# Booster_wire_schematic.net
KiCad netlist of a schematic drawn in EasyEDA
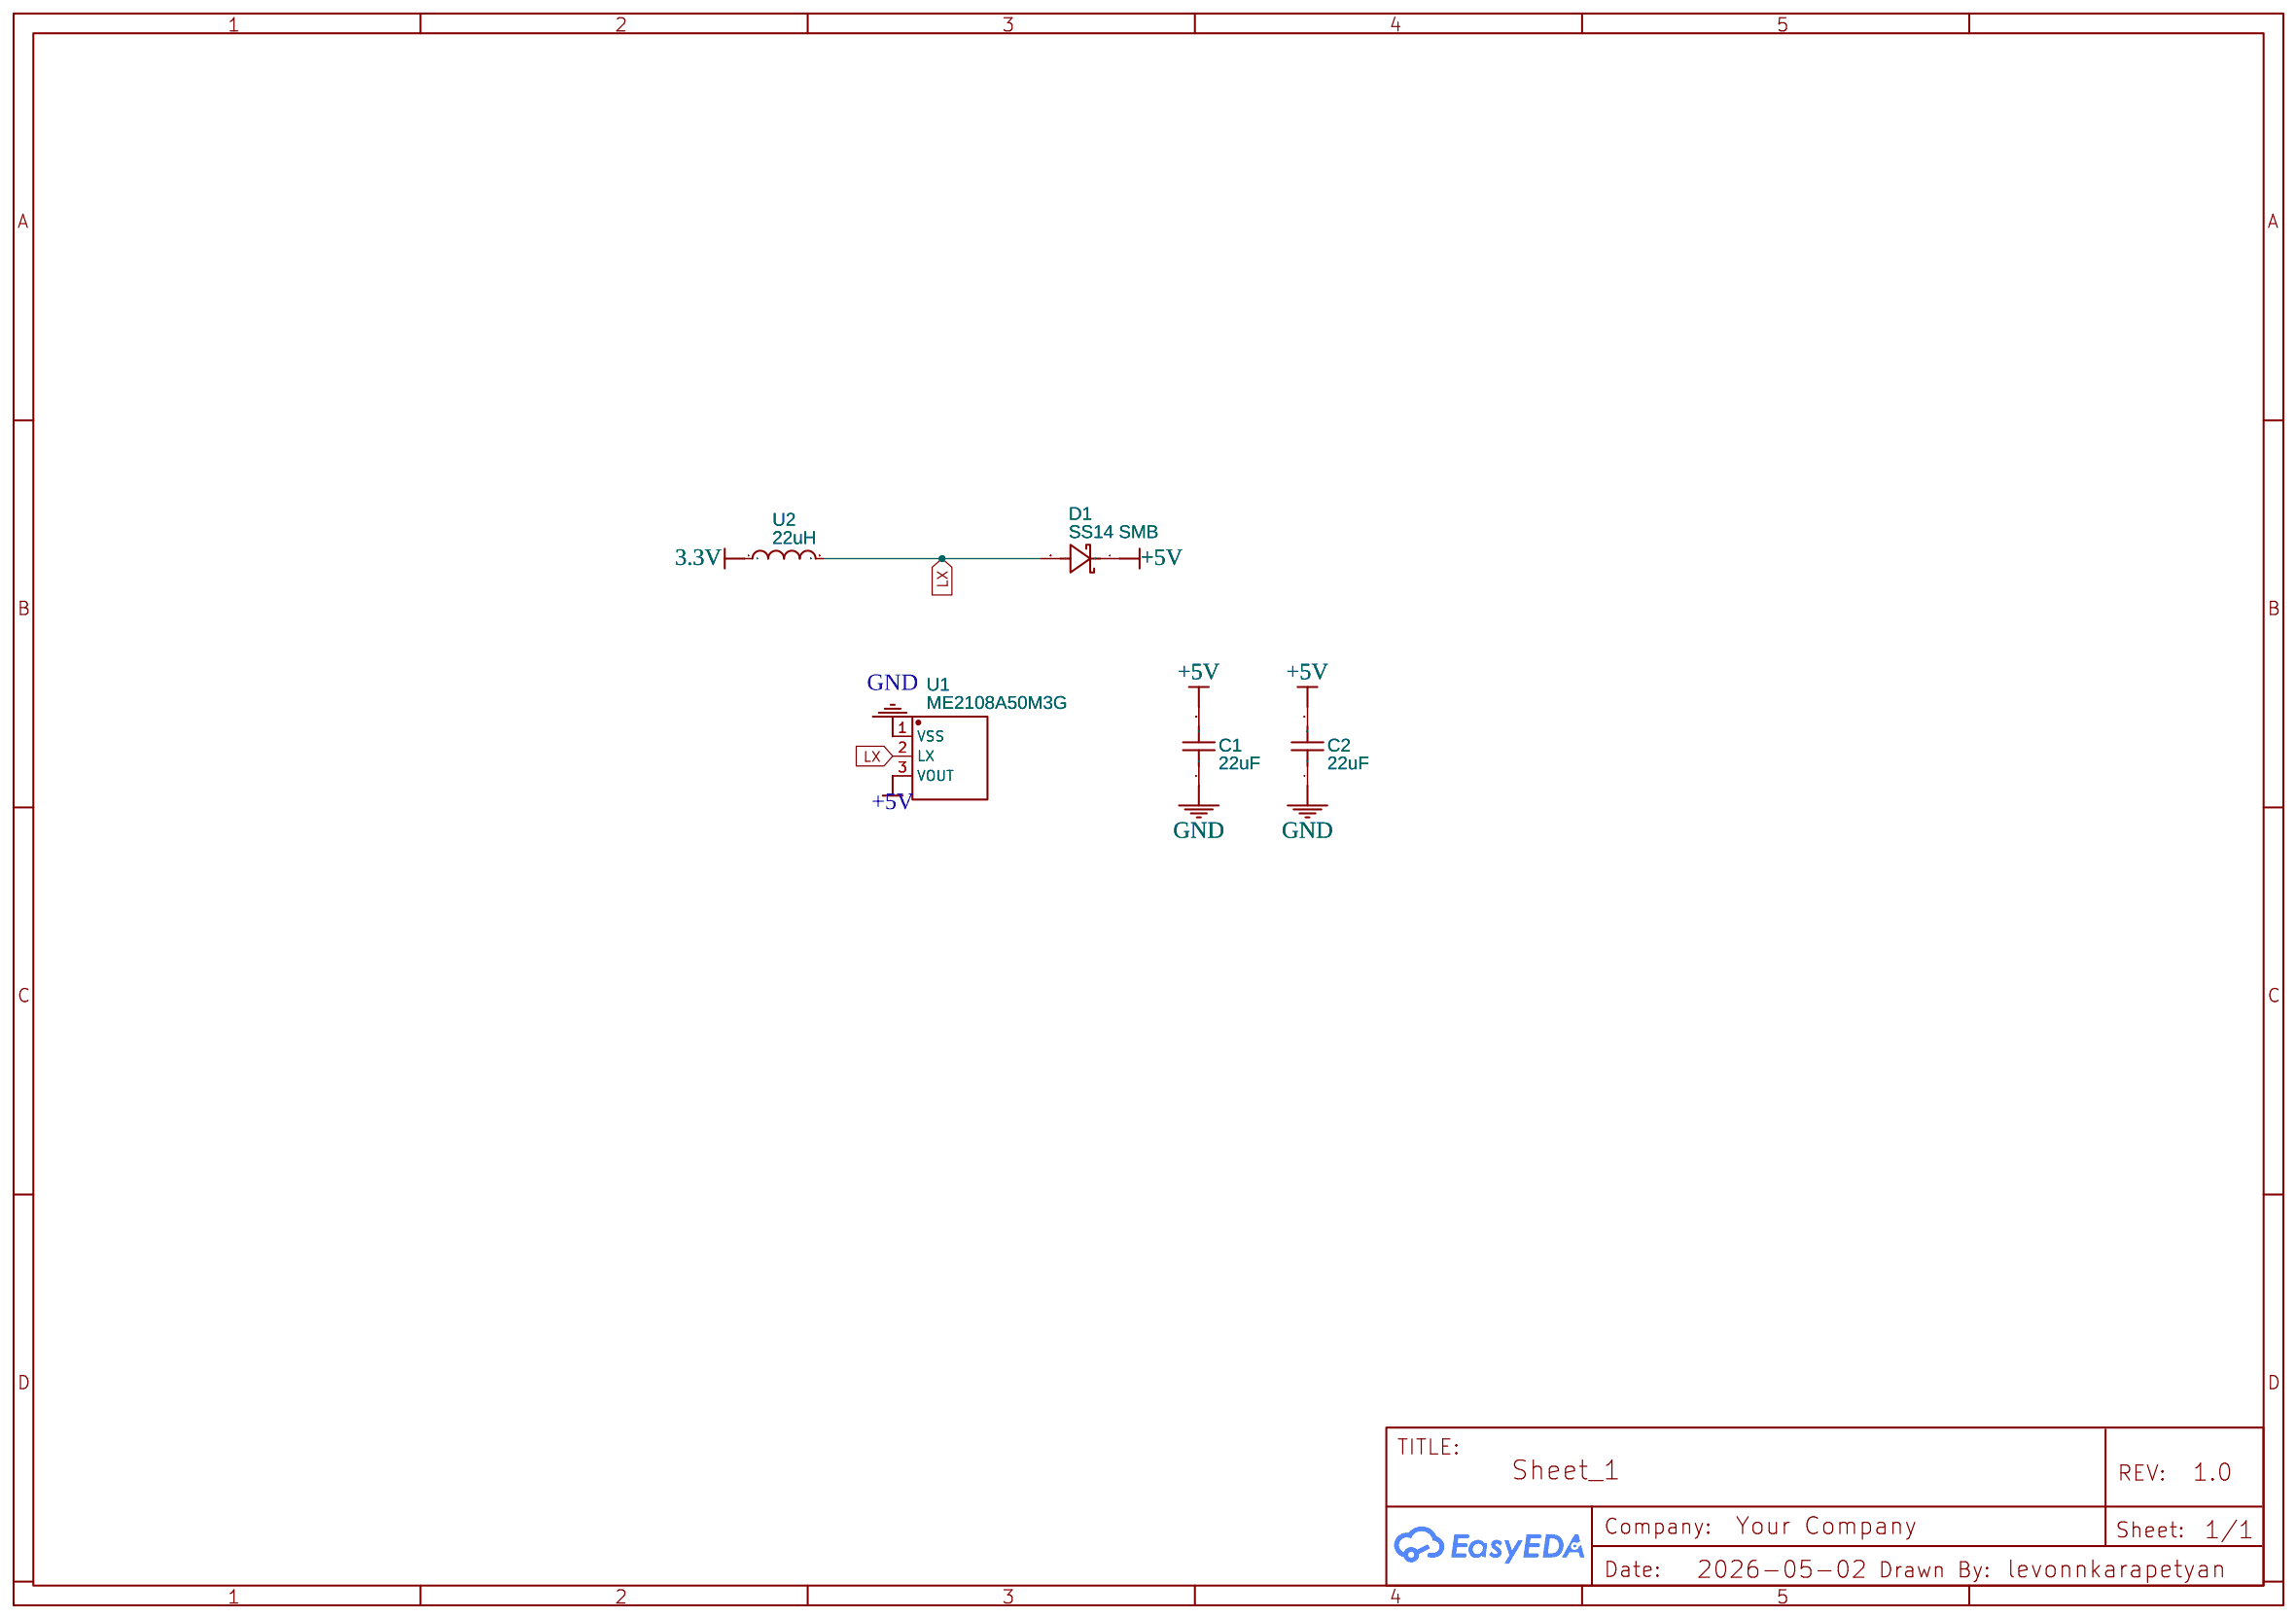
[diagram p0: Booster with net port]
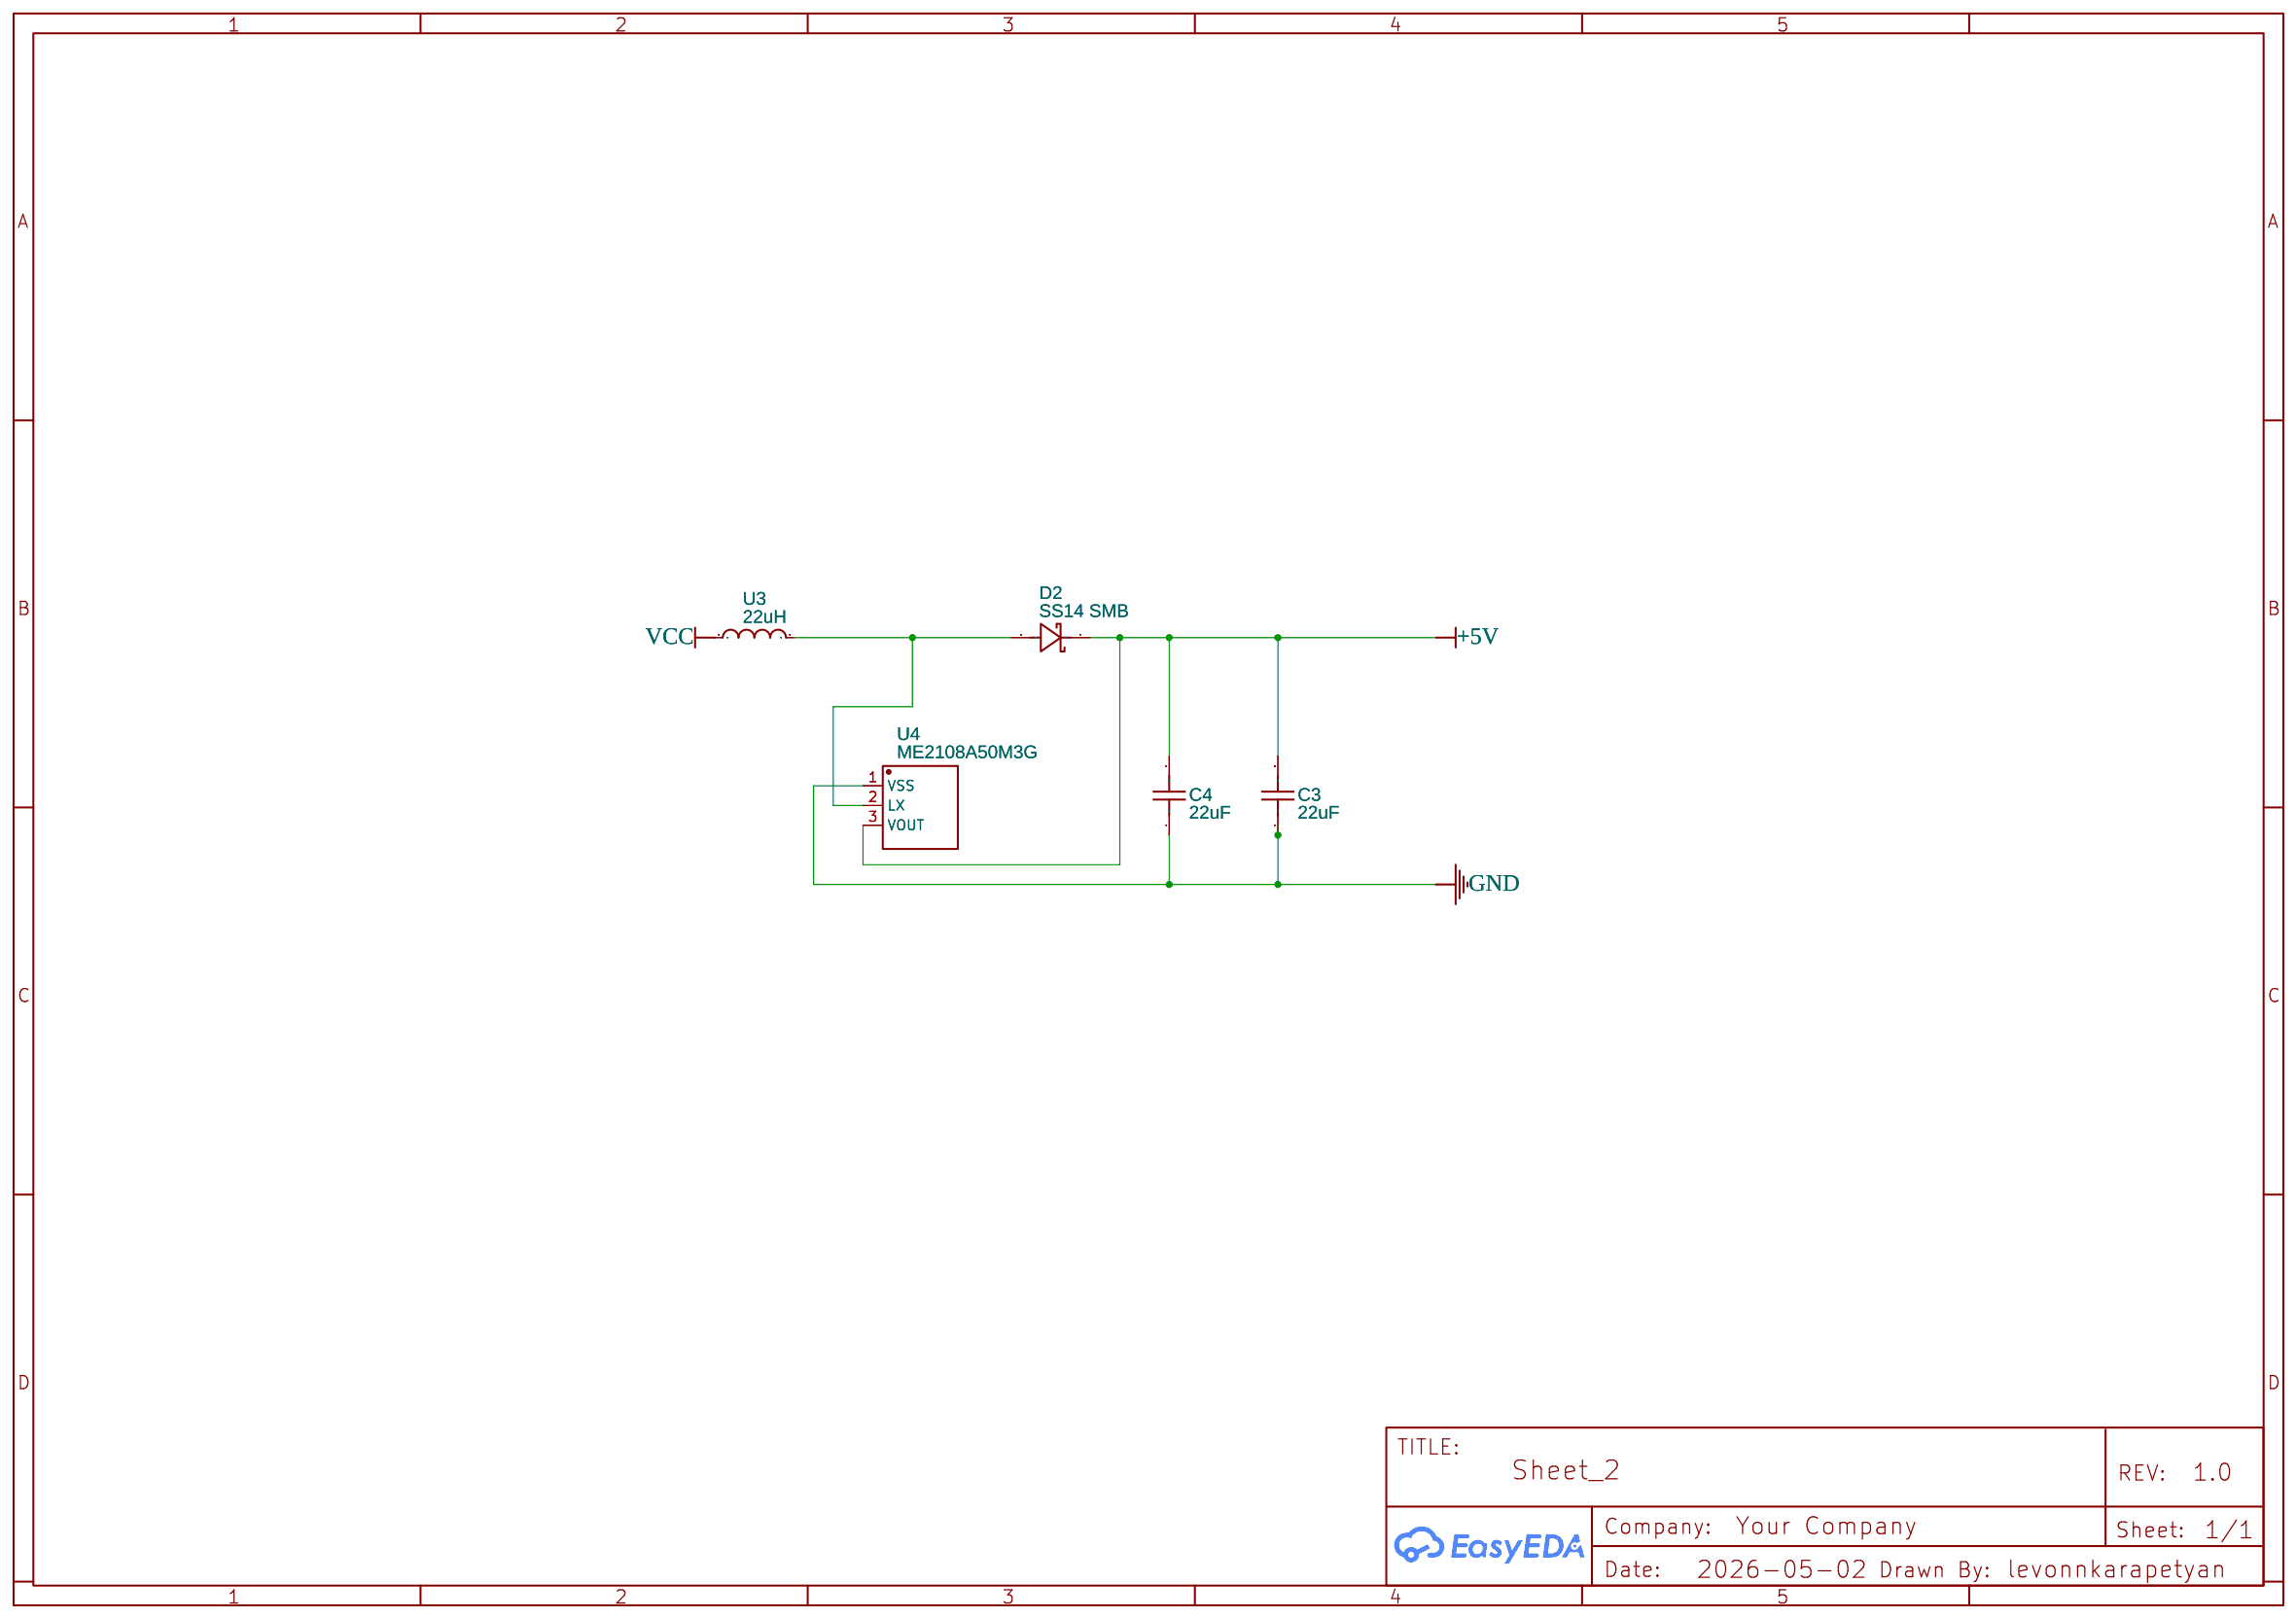
[diagram p1: Booster with wire]

(export (version "E")
  (design (tool "Eeschema 10.0.6"))
  (components
    (comp (ref "C1")
      (value "22uF")
      (fields
        (field (name "Manufacturer Part") "CL21A226MAYNNNE")
        (field (name "Manufacturer") "SAMSUNG(三星)")
      )
      (libsource (lib "") (part "CL21A226MAYNNNE"))
    )
    (comp (ref "C2")
      (value "22uF")
      (fields
        (field (name "Manufacturer Part") "CL21A226MAYNNNE")
        (field (name "Manufacturer") "SAMSUNG(三星)")
      )
      (libsource (lib "") (part "CL21A226MAYNNNE"))
    )
    (comp (ref "D1")
      (value "SS14 SMB")
      (fields (field (name "Manufacturer") "BORN(伯恩半导体)"))
      (libsource (lib "") (part "SS14 SMB"))
    )
    (comp (ref "U1")
      (value "ME2108A50M3G")
      (fields (field (name "Manufacturer") "MICRONE(南京微盟)"))
      (libsource (lib "") (part "ME2108A50M3G"))
    )
    (comp (ref "U2")
      (value "22uH")
      (fields (field (name "Manufacturer Part") "APH0630T220M") (field (name "Manufacturer") "APV(爱普微)"))
      (libsource (lib "") (part "APH0630T220M"))
    )
    (comp (ref "C3")
      (value "22uF")
      (fields
        (field (name "Manufacturer Part") "CL21A226MAYNNNE")
        (field (name "Manufacturer") "SAMSUNG(三星)")
      )
      (libsource (lib "") (part "CL21A226MAYNNNE"))
    )
    (comp (ref "C4")
      (value "22uF")
      (fields
        (field (name "Manufacturer Part") "CL21A226MAYNNNE")
        (field (name "Manufacturer") "SAMSUNG(三星)")
      )
      (libsource (lib "") (part "CL21A226MAYNNNE"))
    )
    (comp (ref "D2")
      (value "SS14 SMB")
      (fields (field (name "Manufacturer") "BORN(伯恩半导体)"))
      (libsource (lib "") (part "SS14 SMB"))
    )
    (comp (ref "U3")
      (value "22uH")
      (fields (field (name "Manufacturer Part") "APH0630T220M") (field (name "Manufacturer") "APV(爱普微)"))
      (libsource (lib "") (part "APH0630T220M"))
    )
    (comp (ref "U4")
      (value "ME2108A50M3G")
      (fields (field (name "Manufacturer") "MICRONE(南京微盟)"))
      (libsource (lib "") (part "ME2108A50M3G"))
    )
  )
  (nets
    (net (code "1") (name "+5V") (class "Default")
      (node (ref "C1") (pin "2") (pinfunction "2_2") (pintype "unspecified"))
      (node (ref "C2") (pin "2") (pinfunction "2_2") (pintype "unspecified"))
      (node (ref "C3") (pin "2") (pinfunction "2_2") (pintype "unspecified"))
      (node (ref "C4") (pin "2") (pinfunction "2_2") (pintype "unspecified"))
      (node (ref "D1") (pin "1") (pinfunction "K_1") (pintype "unspecified"))
      (node (ref "D2") (pin "1") (pinfunction "K_1") (pintype "unspecified"))
      (node (ref "U1") (pin "3") (pinfunction "VOUT_3") (pintype "unspecified"))
      (node (ref "U4") (pin "3") (pinfunction "VOUT_3") (pintype "unspecified"))
    )
    (net (code "2") (name "3.3V") (class "Default")
      (node (ref "U2") (pin "1") (pinfunction "1_1") (pintype "unspecified"))
    )
    (net (code "3") (name "GND") (class "Default")
      (node (ref "C1") (pin "1") (pinfunction "1_1") (pintype "unspecified"))
      (node (ref "C2") (pin "1") (pinfunction "1_1") (pintype "unspecified"))
      (node (ref "C3") (pin "1") (pinfunction "1_1") (pintype "unspecified"))
      (node (ref "C4") (pin "1") (pinfunction "1_1") (pintype "unspecified"))
      (node (ref "U1") (pin "1") (pinfunction "VSS_1") (pintype "unspecified"))
      (node (ref "U4") (pin "1") (pinfunction "VSS_1") (pintype "unspecified"))
    )
    (net (code "4") (name "LX") (class "Default")
      (node (ref "D1") (pin "2") (pinfunction "A_2") (pintype "unspecified"))
      (node (ref "U1") (pin "2") (pinfunction "LX_2") (pintype "unspecified"))
      (node (ref "U2") (pin "2") (pinfunction "2_2") (pintype "unspecified"))
    )
    (net (code "5") (name "Net-(D2-A)") (class "Default")
      (node (ref "D2") (pin "2") (pinfunction "A_2") (pintype "unspecified"))
      (node (ref "U3") (pin "2") (pinfunction "2_2") (pintype "unspecified"))
      (node (ref "U4") (pin "2") (pinfunction "LX_2") (pintype "unspecified"))
    )
    (net (code "6") (name "VCC") (class "Default")
      (node (ref "U3") (pin "1") (pinfunction "1_1") (pintype "unspecified"))
    )
  )
)
